# RectangularThing-LEDs.net
KiCad netlist of a schematic drawn in EAGLE
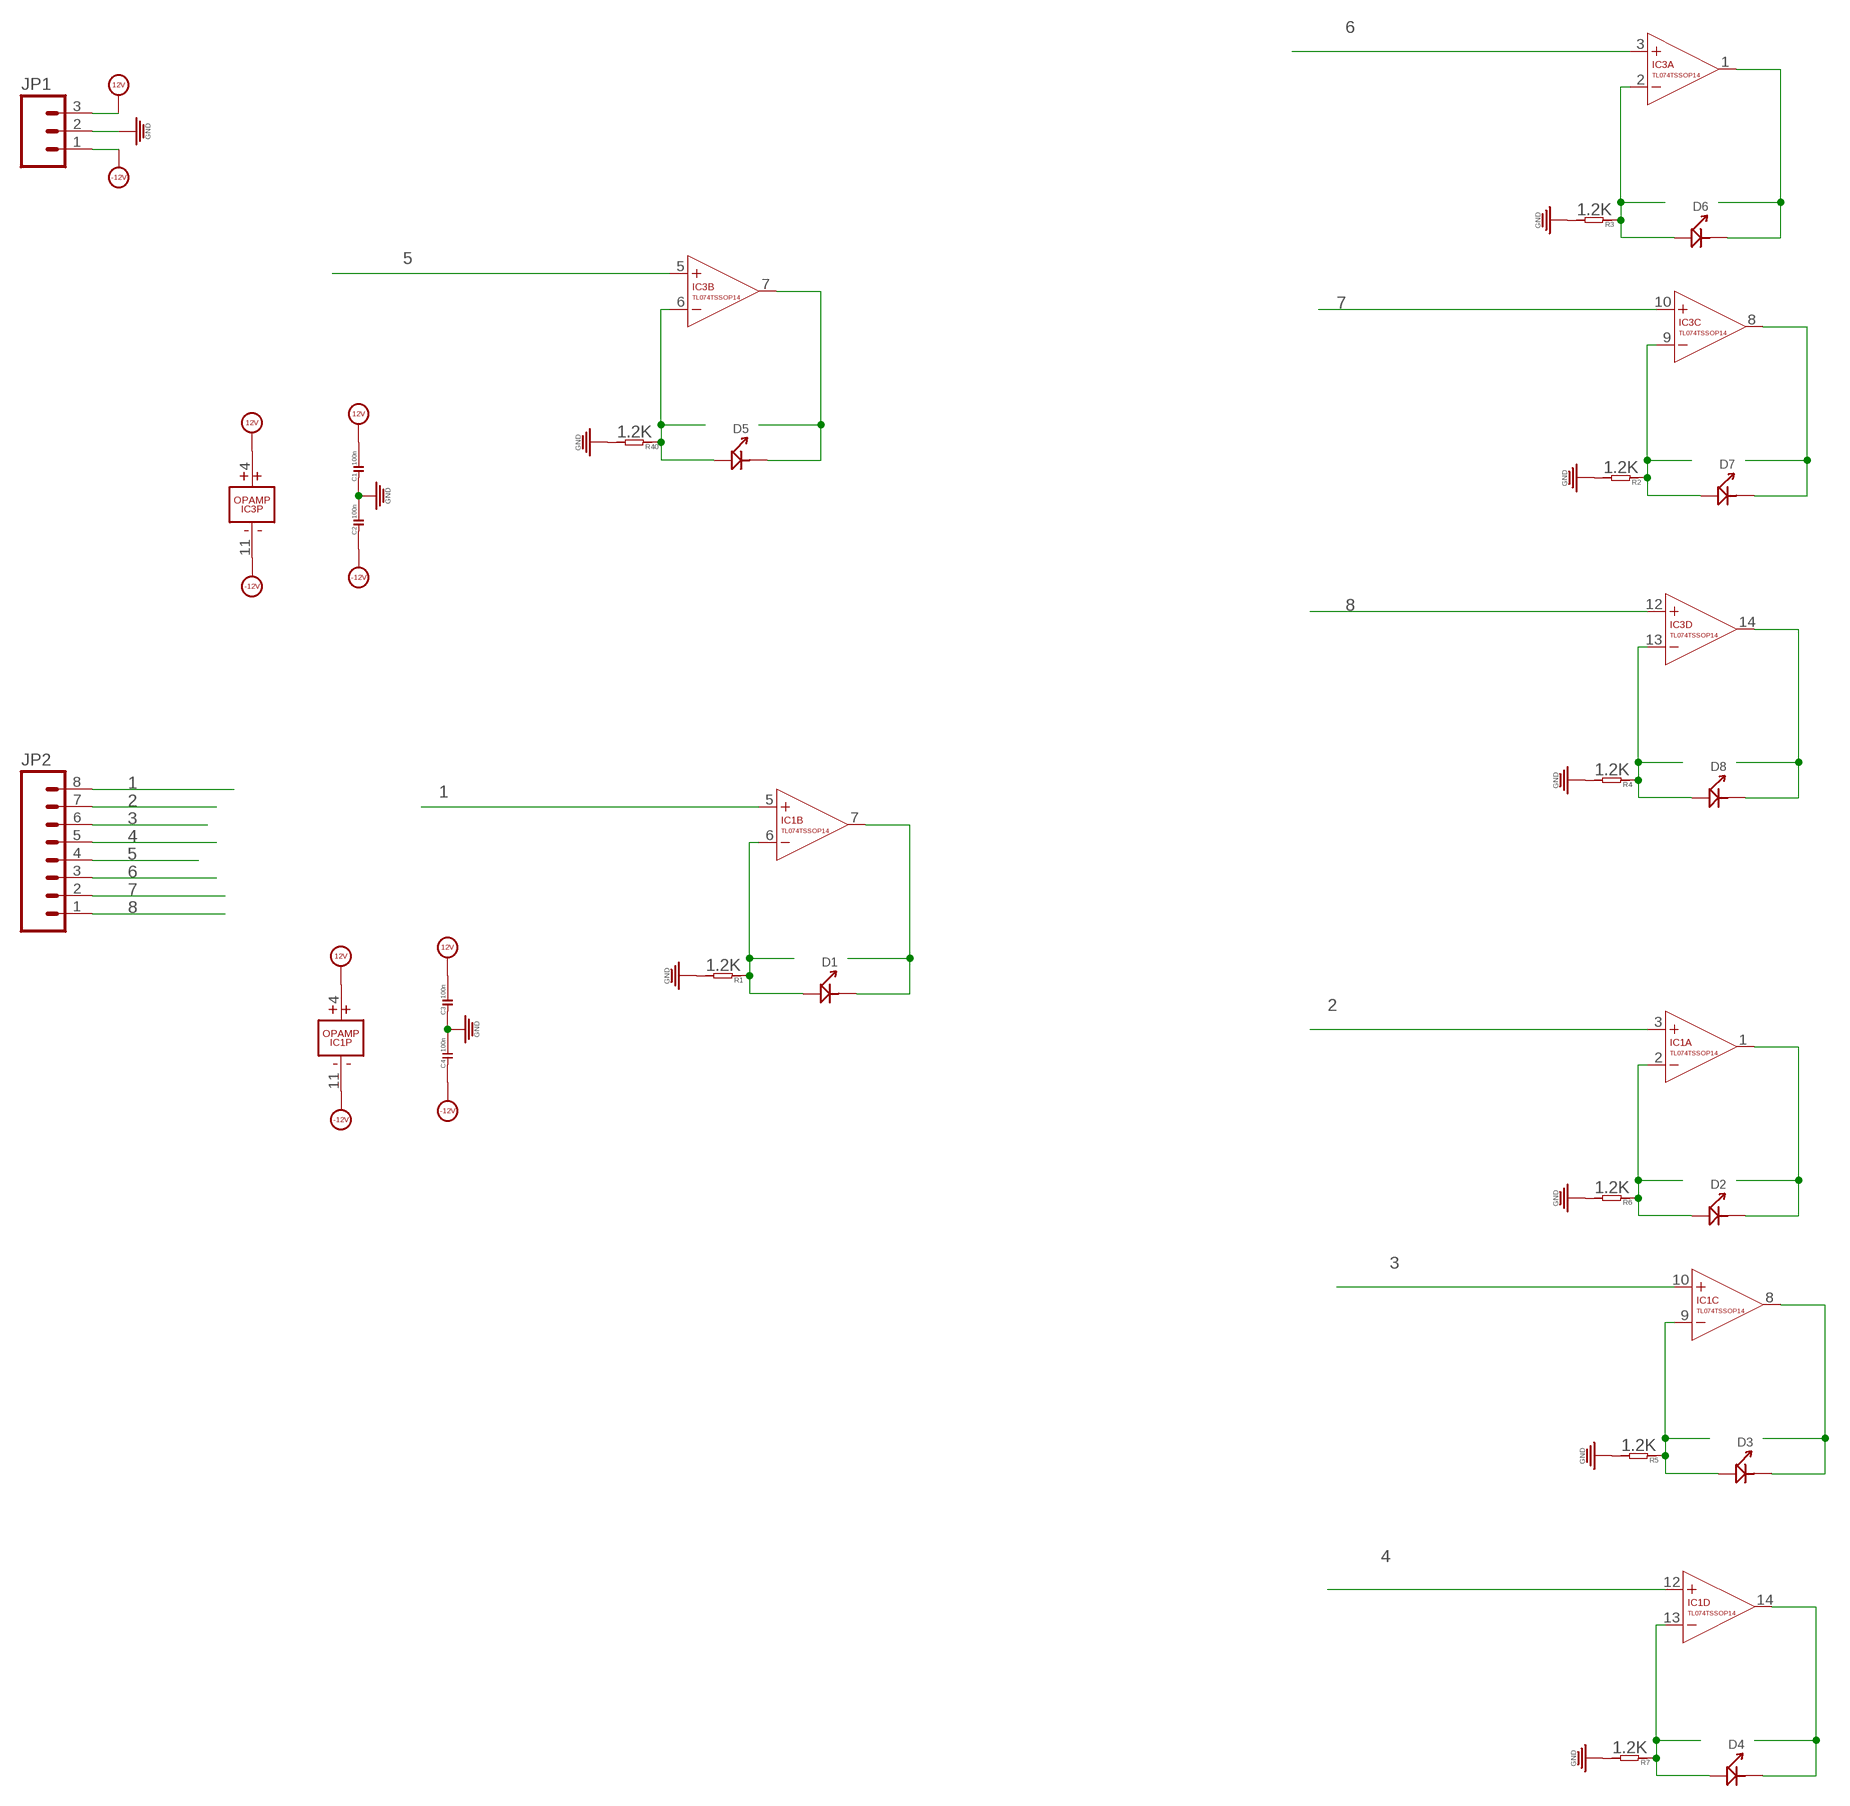
[diagram p0: schematic, sheet 1]

(export (version "E")
  (design (tool "Eeschema 10.0.6"))
  (components
    (comp (ref "C1")
      (value "100n")
      (footprint "eagle-import:C0603")
      (libsource (lib "eagle-import") (part "C-0603"))
    )
    (comp (ref "C2")
      (value "100n")
      (footprint "eagle-import:C0603")
      (libsource (lib "eagle-import") (part "C-0603"))
    )
    (comp (ref "C3")
      (value "100n")
      (footprint "eagle-import:C0603")
      (libsource (lib "eagle-import") (part "C-0603"))
    )
    (comp (ref "C4")
      (value "100n")
      (footprint "eagle-import:C0603")
      (libsource (lib "eagle-import") (part "C-0603"))
    )
    (comp (ref "D1")
      (value "LED")
      (footprint "eagle-import:LED0603")
      (libsource (lib "eagle-import") (part "LED"))
    )
    (comp (ref "D2")
      (value "LED")
      (footprint "eagle-import:LED0603")
      (libsource (lib "eagle-import") (part "LED"))
    )
    (comp (ref "D3")
      (value "LED")
      (footprint "eagle-import:LED0603")
      (libsource (lib "eagle-import") (part "LED"))
    )
    (comp (ref "D4")
      (value "LED")
      (footprint "eagle-import:LED0603")
      (libsource (lib "eagle-import") (part "LED"))
    )
    (comp (ref "D5")
      (value "LED")
      (footprint "eagle-import:LED0603")
      (libsource (lib "eagle-import") (part "LED"))
    )
    (comp (ref "D6")
      (value "LED")
      (footprint "eagle-import:LED0603")
      (libsource (lib "eagle-import") (part "LED"))
    )
    (comp (ref "D7")
      (value "LED")
      (footprint "eagle-import:LED0603")
      (libsource (lib "eagle-import") (part "LED"))
    )
    (comp (ref "D8")
      (value "LED")
      (footprint "eagle-import:LED0603")
      (libsource (lib "eagle-import") (part "LED"))
    )
    (comp (ref "IC1")
      (value "TL074TSSOP14")
      (footprint "eagle-import:TSSOP14")
      (libsource (lib "eagle-import") (part "TL074TSSOP14"))
    )
    (comp (ref "IC3")
      (value "TL074TSSOP14")
      (footprint "eagle-import:TSSOP14")
      (libsource (lib "eagle-import") (part "TL074TSSOP14"))
    )
    (comp (ref "JP1")
      (value "M03PTH")
      (footprint "eagle-import:1X03")
      (libsource (lib "eagle-import") (part "M03PTH"))
    )
    (comp (ref "JP2")
      (value "M08LONGPADS")
      (footprint "eagle-import:1X08_LONGPADS")
      (libsource (lib "eagle-import") (part "M08LONGPADS"))
    )
    (comp (ref "R1")
      (value "1.2K")
      (footprint "eagle-import:R0603")
      (libsource (lib "eagle-import") (part "R-0603"))
    )
    (comp (ref "R2")
      (value "1.2K")
      (footprint "eagle-import:R0603")
      (libsource (lib "eagle-import") (part "R-0603"))
    )
    (comp (ref "R3")
      (value "1.2K")
      (footprint "eagle-import:R0603")
      (libsource (lib "eagle-import") (part "R-0603"))
    )
    (comp (ref "R4")
      (value "1.2K")
      (footprint "eagle-import:R0603")
      (libsource (lib "eagle-import") (part "R-0603"))
    )
    (comp (ref "R5")
      (value "1.2K")
      (footprint "eagle-import:R0603")
      (libsource (lib "eagle-import") (part "R-0603"))
    )
    (comp (ref "R6")
      (value "1.2K")
      (footprint "eagle-import:R0603")
      (libsource (lib "eagle-import") (part "R-0603"))
    )
    (comp (ref "R7")
      (value "1.2K")
      (footprint "eagle-import:R0603")
      (libsource (lib "eagle-import") (part "R-0603"))
    )
    (comp (ref "R40")
      (value "1.2K")
      (footprint "eagle-import:R0603")
      (libsource (lib "eagle-import") (part "R-0603"))
    )
  )
  (nets
    (net (code "1") (name "-12V") (class "Default")
      (node (ref "C2") (pin "1") (pinfunction "1_1") (pintype "bidirectional"))
      (node (ref "C4") (pin "1") (pinfunction "1_1") (pintype "bidirectional"))
      (node (ref "IC1") (pin "11") (pinfunction "V-_11") (pintype "power_in"))
      (node (ref "IC3") (pin "11") (pinfunction "V-_11") (pintype "power_in"))
      (node (ref "JP1") (pin "1") (pinfunction "1_1") (pintype "passive"))
    )
    (net (code "2") (name "/1") (class "Default")
      (node (ref "IC1") (pin "5") (pinfunction "+IN_5") (pintype "input"))
      (node (ref "JP2") (pin "8") (pinfunction "8_8") (pintype "passive"))
    )
    (net (code "3") (name "/2") (class "Default")
      (node (ref "IC1") (pin "3") (pinfunction "+IN_3") (pintype "input"))
      (node (ref "JP2") (pin "7") (pinfunction "7_7") (pintype "passive"))
    )
    (net (code "4") (name "/3") (class "Default")
      (node (ref "IC1") (pin "10") (pinfunction "+IN_10") (pintype "input"))
      (node (ref "JP2") (pin "6") (pinfunction "6_6") (pintype "passive"))
    )
    (net (code "5") (name "/4") (class "Default")
      (node (ref "IC1") (pin "12") (pinfunction "+IN_12") (pintype "input"))
      (node (ref "JP2") (pin "5") (pinfunction "5_5") (pintype "passive"))
    )
    (net (code "6") (name "/5") (class "Default")
      (node (ref "IC3") (pin "5") (pinfunction "+IN_5") (pintype "input"))
      (node (ref "JP2") (pin "4") (pinfunction "4_4") (pintype "passive"))
    )
    (net (code "7") (name "/6") (class "Default")
      (node (ref "IC3") (pin "3") (pinfunction "+IN_3") (pintype "input"))
      (node (ref "JP2") (pin "3") (pinfunction "3_3") (pintype "passive"))
    )
    (net (code "8") (name "/7") (class "Default")
      (node (ref "IC3") (pin "10") (pinfunction "+IN_10") (pintype "input"))
      (node (ref "JP2") (pin "2") (pinfunction "2_2") (pintype "passive"))
    )
    (net (code "9") (name "/8") (class "Default")
      (node (ref "IC3") (pin "12") (pinfunction "+IN_12") (pintype "input"))
      (node (ref "JP2") (pin "1") (pinfunction "1_1") (pintype "passive"))
    )
    (net (code "10") (name "12V") (class "Default")
      (node (ref "C1") (pin "2") (pinfunction "2_2") (pintype "bidirectional"))
      (node (ref "C3") (pin "2") (pinfunction "2_2") (pintype "bidirectional"))
      (node (ref "IC1") (pin "4") (pinfunction "V+_4") (pintype "power_in"))
      (node (ref "IC3") (pin "4") (pinfunction "V+_4") (pintype "power_in"))
      (node (ref "JP1") (pin "3") (pinfunction "3_3") (pintype "passive"))
    )
    (net (code "11") (name "GND") (class "Default")
      (node (ref "C1") (pin "1") (pinfunction "1_1") (pintype "bidirectional"))
      (node (ref "C2") (pin "2") (pinfunction "2_2") (pintype "bidirectional"))
      (node (ref "C3") (pin "1") (pinfunction "1_1") (pintype "bidirectional"))
      (node (ref "C4") (pin "2") (pinfunction "2_2") (pintype "bidirectional"))
      (node (ref "JP1") (pin "2") (pinfunction "2_2") (pintype "passive"))
      (node (ref "R1") (pin "2") (pinfunction "2_2") (pintype "bidirectional"))
      (node (ref "R2") (pin "2") (pinfunction "2_2") (pintype "bidirectional"))
      (node (ref "R3") (pin "2") (pinfunction "2_2") (pintype "bidirectional"))
      (node (ref "R4") (pin "2") (pinfunction "2_2") (pintype "bidirectional"))
      (node (ref "R40") (pin "2") (pinfunction "2_2") (pintype "bidirectional"))
      (node (ref "R5") (pin "2") (pinfunction "2_2") (pintype "bidirectional"))
      (node (ref "R6") (pin "2") (pinfunction "2_2") (pintype "bidirectional"))
      (node (ref "R7") (pin "2") (pinfunction "2_2") (pintype "bidirectional"))
    )
    (net (code "12") (name "Net-(IC1A--IN)") (class "Default")
      (node (ref "D2") (pin "+") (pinfunction "+_+") (pintype "passive"))
      (node (ref "IC1") (pin "2") (pinfunction "-IN_2") (pintype "input"))
      (node (ref "R6") (pin "1") (pinfunction "1_1") (pintype "bidirectional"))
    )
    (net (code "13") (name "Net-(IC1A-OUT)") (class "Default")
      (node (ref "D2") (pin "-") (pinfunction "-_-") (pintype "passive"))
      (node (ref "IC1") (pin "1") (pinfunction "OUT_1") (pintype "output"))
    )
    (net (code "14") (name "Net-(IC1B--IN)") (class "Default")
      (node (ref "D1") (pin "+") (pinfunction "+_+") (pintype "passive"))
      (node (ref "IC1") (pin "6") (pinfunction "-IN_6") (pintype "input"))
      (node (ref "R1") (pin "1") (pinfunction "1_1") (pintype "bidirectional"))
    )
    (net (code "15") (name "Net-(IC1B-OUT)") (class "Default")
      (node (ref "D1") (pin "-") (pinfunction "-_-") (pintype "passive"))
      (node (ref "IC1") (pin "7") (pinfunction "OUT_7") (pintype "output"))
    )
    (net (code "16") (name "Net-(IC1C--IN)") (class "Default")
      (node (ref "D3") (pin "+") (pinfunction "+_+") (pintype "passive"))
      (node (ref "IC1") (pin "9") (pinfunction "-IN_9") (pintype "input"))
      (node (ref "R5") (pin "1") (pinfunction "1_1") (pintype "bidirectional"))
    )
    (net (code "17") (name "Net-(IC1C-OUT)") (class "Default")
      (node (ref "D3") (pin "-") (pinfunction "-_-") (pintype "passive"))
      (node (ref "IC1") (pin "8") (pinfunction "OUT_8") (pintype "output"))
    )
    (net (code "18") (name "Net-(IC1D--IN)") (class "Default")
      (node (ref "D4") (pin "+") (pinfunction "+_+") (pintype "passive"))
      (node (ref "IC1") (pin "13") (pinfunction "-IN_13") (pintype "input"))
      (node (ref "R7") (pin "1") (pinfunction "1_1") (pintype "bidirectional"))
    )
    (net (code "19") (name "Net-(IC1D-OUT)") (class "Default")
      (node (ref "D4") (pin "-") (pinfunction "-_-") (pintype "passive"))
      (node (ref "IC1") (pin "14") (pinfunction "OUT_14") (pintype "output"))
    )
    (net (code "20") (name "Net-(IC3A--IN)") (class "Default")
      (node (ref "D6") (pin "+") (pinfunction "+_+") (pintype "passive"))
      (node (ref "IC3") (pin "2") (pinfunction "-IN_2") (pintype "input"))
      (node (ref "R3") (pin "1") (pinfunction "1_1") (pintype "bidirectional"))
    )
    (net (code "21") (name "Net-(IC3A-OUT)") (class "Default")
      (node (ref "D6") (pin "-") (pinfunction "-_-") (pintype "passive"))
      (node (ref "IC3") (pin "1") (pinfunction "OUT_1") (pintype "output"))
    )
    (net (code "22") (name "Net-(IC3B--IN)") (class "Default")
      (node (ref "D5") (pin "+") (pinfunction "+_+") (pintype "passive"))
      (node (ref "IC3") (pin "6") (pinfunction "-IN_6") (pintype "input"))
      (node (ref "R40") (pin "1") (pinfunction "1_1") (pintype "bidirectional"))
    )
    (net (code "23") (name "Net-(IC3B-OUT)") (class "Default")
      (node (ref "D5") (pin "-") (pinfunction "-_-") (pintype "passive"))
      (node (ref "IC3") (pin "7") (pinfunction "OUT_7") (pintype "output"))
    )
    (net (code "24") (name "Net-(IC3C--IN)") (class "Default")
      (node (ref "D7") (pin "+") (pinfunction "+_+") (pintype "passive"))
      (node (ref "IC3") (pin "9") (pinfunction "-IN_9") (pintype "input"))
      (node (ref "R2") (pin "1") (pinfunction "1_1") (pintype "bidirectional"))
    )
    (net (code "25") (name "Net-(IC3C-OUT)") (class "Default")
      (node (ref "D7") (pin "-") (pinfunction "-_-") (pintype "passive"))
      (node (ref "IC3") (pin "8") (pinfunction "OUT_8") (pintype "output"))
    )
    (net (code "26") (name "Net-(IC3D--IN)") (class "Default")
      (node (ref "D8") (pin "+") (pinfunction "+_+") (pintype "passive"))
      (node (ref "IC3") (pin "13") (pinfunction "-IN_13") (pintype "input"))
      (node (ref "R4") (pin "1") (pinfunction "1_1") (pintype "bidirectional"))
    )
    (net (code "27") (name "Net-(IC3D-OUT)") (class "Default")
      (node (ref "D8") (pin "-") (pinfunction "-_-") (pintype "passive"))
      (node (ref "IC3") (pin "14") (pinfunction "OUT_14") (pintype "output"))
    )
  )
)
